# sensor-header.net
KiCad netlist of a schematic drawn in Altium Designer
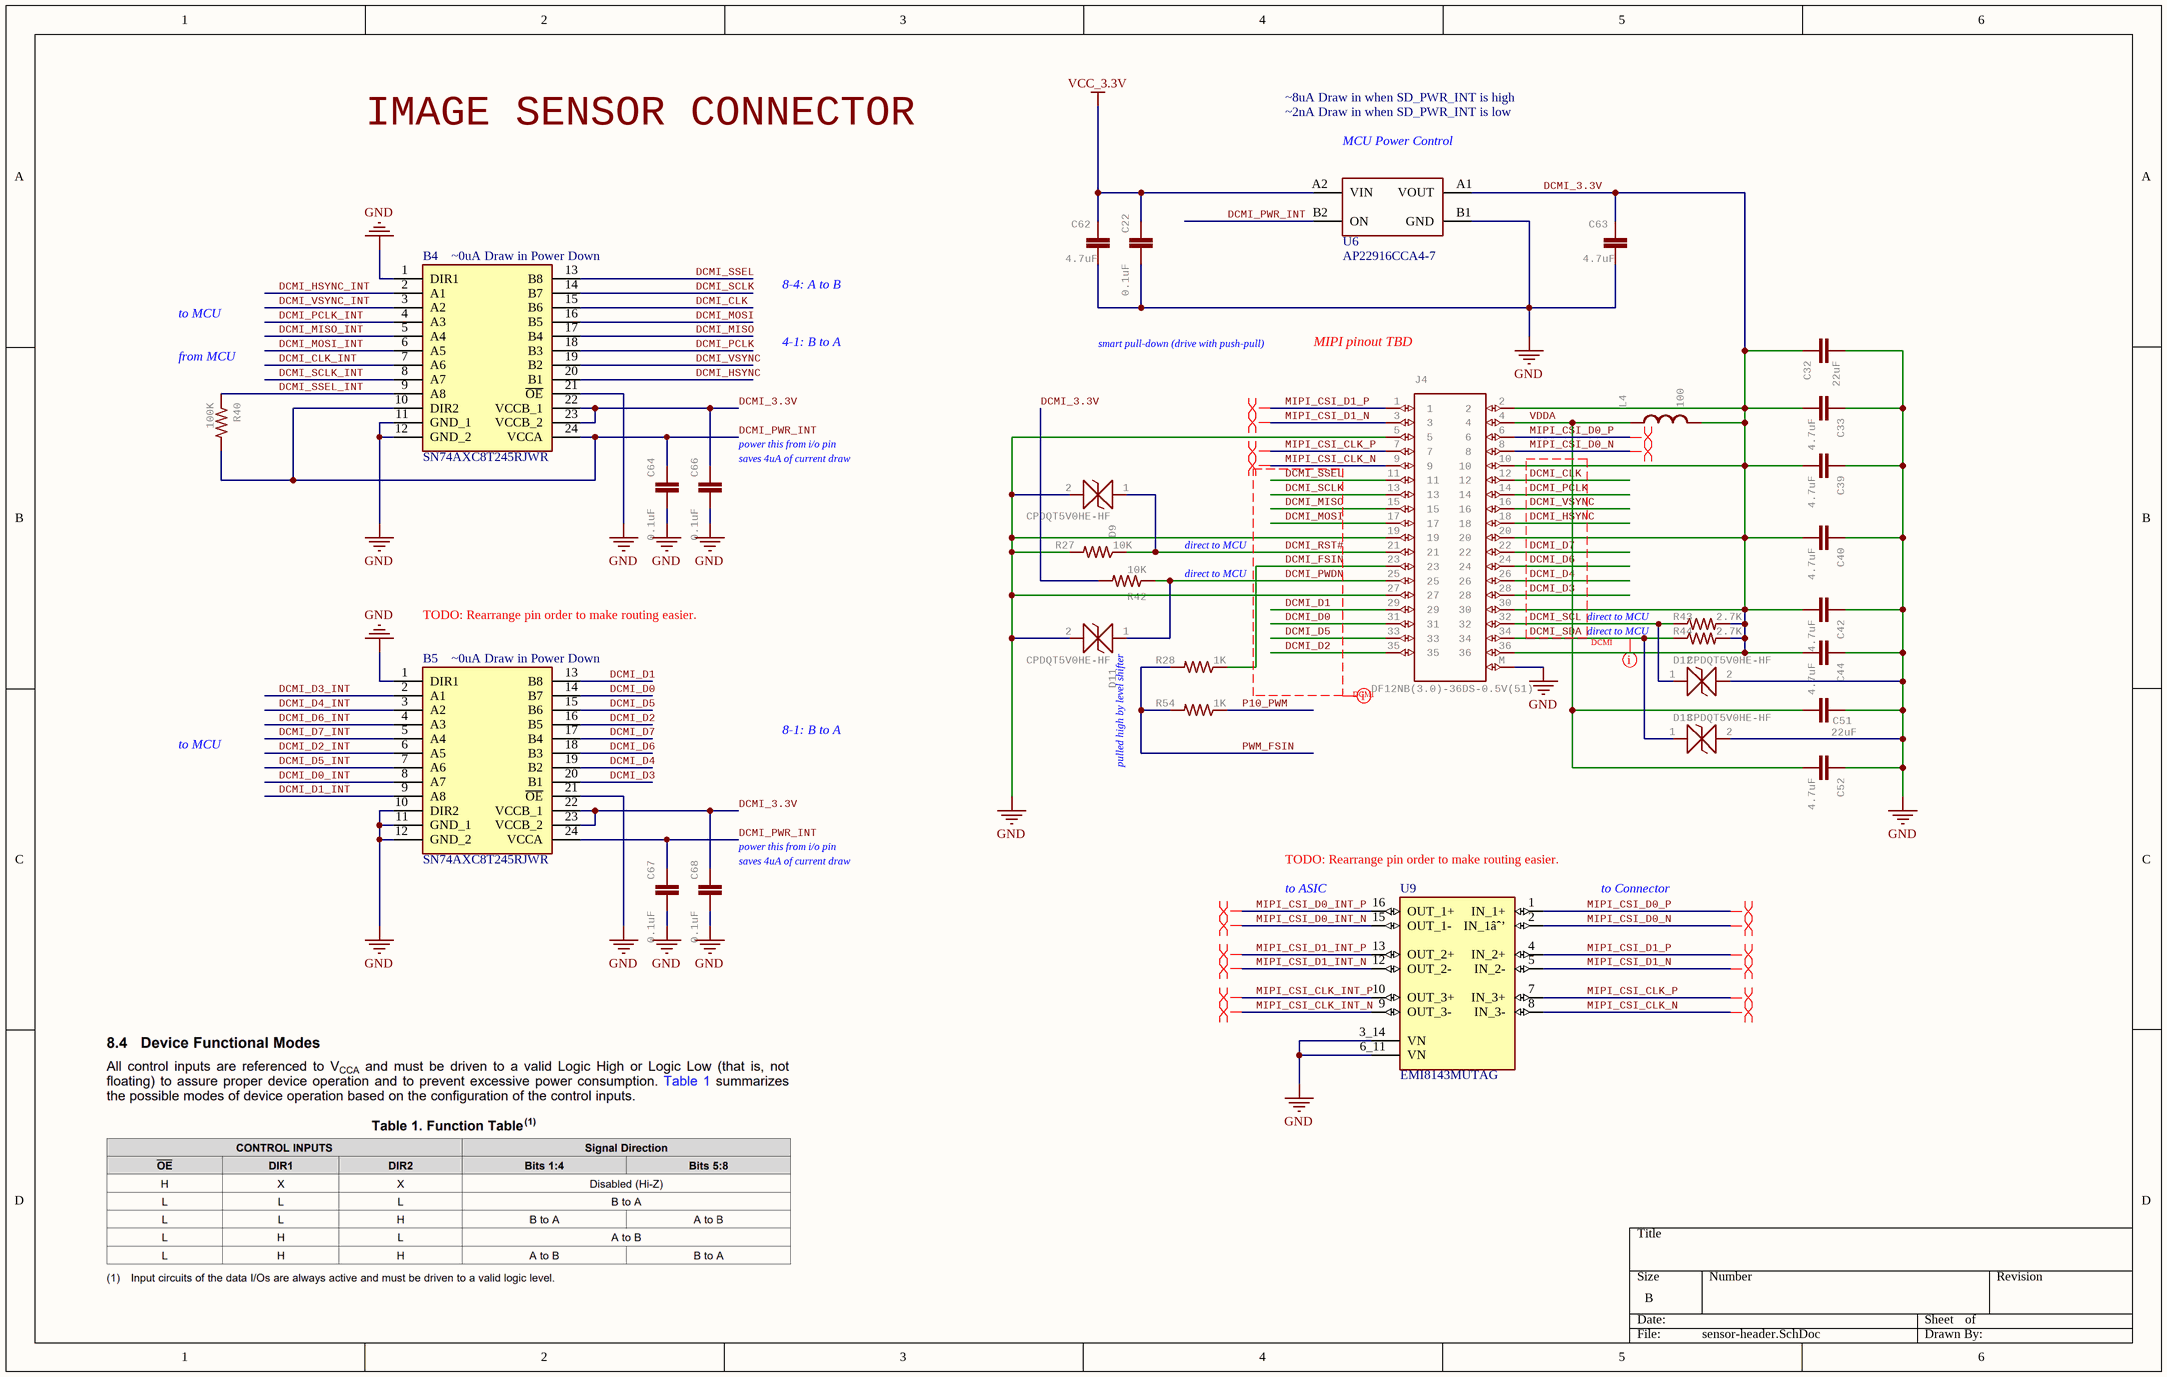
[diagram p0: sensor-header.SchDoc]

(export (version "E")
  (design (tool "Eeschema 10.0.6"))
  (components
    (comp (ref "B4")
      (value "SN74AXC8T245RJWR")
      (footprint "SN74AXC8T245RJWR")
      (description "8-Bit Dual-Supply Bus Transceiver")
      (fields (field (name "MOUSER PART NUMBER") "595-SN74AXC8T245RJWR"))
      (libsource (lib "openmv-ae3") (part "SN74AXC8T245RJWR"))
    )
    (comp (ref "B5")
      (value "SN74AXC8T245RJWR")
      (footprint "SN74AXC8T245RJWR")
      (description "8-Bit Dual-Supply Bus Transceiver")
      (fields (field (name "MOUSER PART NUMBER") "595-SN74AXC8T245RJWR"))
      (libsource (lib "openmv-ae3") (part "SN74AXC8T245RJWR"))
    )
    (comp (ref "C22")
      (value "0.1uF")
      (footprint "0402-CAP")
      (description "CAPACITOR, European symbol")
      (fields (field (name "MPN") "C0402C104Z4VAC"))
      (libsource (lib "openmv-ae3") (part "C-EUC0201"))
    )
    (comp (ref "C32")
      (value "22uF")
      (footprint "0805")
      (fields (field (name "MPN") "CL21A226MQQNNNE"))
      (libsource (lib "openmv-ae3") (part "22UF-0805-6.3V-20%"))
    )
    (comp (ref "C33")
      (value "4.7uF")
      (footprint "0402-CAP")
      (description "CapacitorStandard 0603 ceramic capacitor, and 0.1\" leaded capacitor.")
      (fields (field (name "MPN") "JMK105BBJ475MV-F") (field (name "LIBRARYNAME") "sfe"))
      (libsource (lib "openmv-ae3") (part "CAP0402-CAP"))
    )
    (comp (ref "C39")
      (value "4.7uF")
      (footprint "0402-CAP")
      (description "CapacitorStandard 0603 ceramic capacitor, and 0.1\" leaded capacitor.")
      (fields (field (name "MPN") "JMK105BBJ475MV-F") (field (name "LIBRARYNAME") "sfe"))
      (libsource (lib "openmv-ae3") (part "CAP0402-CAP"))
    )
    (comp (ref "C40")
      (value "4.7uF")
      (footprint "0402-CAP")
      (description "CapacitorStandard 0603 ceramic capacitor, and 0.1\" leaded capacitor.")
      (fields (field (name "MPN") "JMK105BBJ475MV-F") (field (name "LIBRARYNAME") "sfe"))
      (libsource (lib "openmv-ae3") (part "CAP0402-CAP"))
    )
    (comp (ref "C42")
      (value "4.7uF")
      (footprint "0402-CAP")
      (description "CapacitorStandard 0603 ceramic capacitor, and 0.1\" leaded capacitor.")
      (fields (field (name "MPN") "JMK105BBJ475MV-F") (field (name "LIBRARYNAME") "sfe"))
      (libsource (lib "openmv-ae3") (part "CAP0402-CAP"))
    )
    (comp (ref "C44")
      (value "4.7uF")
      (footprint "0402-CAP")
      (description "CapacitorStandard 0603 ceramic capacitor, and 0.1\" leaded capacitor.")
      (fields (field (name "MPN") "JMK105BBJ475MV-F") (field (name "LIBRARYNAME") "sfe"))
      (libsource (lib "openmv-ae3") (part "CAP0402-CAP"))
    )
    (comp (ref "C51")
      (value "22uF")
      (footprint "0805")
      (fields (field (name "MPN") "CL21A226MQQNNNE"))
      (libsource (lib "openmv-ae3") (part "22UF-0805-6.3V-20%"))
    )
    (comp (ref "C52")
      (value "4.7uF")
      (footprint "0402-CAP")
      (description "CapacitorStandard 0603 ceramic capacitor, and 0.1\" leaded capacitor.")
      (fields (field (name "MPN") "JMK105BBJ475MV-F") (field (name "LIBRARYNAME") "sfe"))
      (libsource (lib "openmv-ae3") (part "CAP0402-CAP"))
    )
    (comp (ref "C62")
      (value "4.7uF")
      (footprint "0402-CAP")
      (description "CapacitorStandard 0603 ceramic capacitor, and 0.1\" leaded capacitor.")
      (fields (field (name "MPN") "JMK105BBJ475MV-F") (field (name "LIBRARYNAME") "sfe"))
      (libsource (lib "") (part "CAP0402-CAP_1"))
    )
    (comp (ref "C63")
      (value "4.7uF")
      (footprint "0402-CAP")
      (description "CapacitorStandard 0603 ceramic capacitor, and 0.1\" leaded capacitor.")
      (fields (field (name "MPN") "JMK105BBJ475MV-F") (field (name "LIBRARYNAME") "sfe"))
      (libsource (lib "") (part "CAP0402-CAP_1"))
    )
    (comp (ref "C64")
      (value "0.1uF")
      (footprint "0402-CAP")
      (description "CAPACITOR, European symbol")
      (fields (field (name "MPN") "C0402C104Z4VAC"))
      (libsource (lib "openmv-ae3") (part "C-EUC0201"))
    )
    (comp (ref "C66")
      (value "0.1uF")
      (footprint "0402-CAP")
      (description "CAPACITOR, European symbol")
      (fields (field (name "MPN") "C0402C104Z4VAC"))
      (libsource (lib "openmv-ae3") (part "C-EUC0201"))
    )
    (comp (ref "C67")
      (value "0.1uF")
      (footprint "0402-CAP")
      (description "CAPACITOR, European symbol")
      (fields (field (name "MPN") "C0402C104Z4VAC"))
      (libsource (lib "openmv-ae3") (part "C-EUC0201"))
    )
    (comp (ref "C68")
      (value "0.1uF")
      (footprint "0402-CAP")
      (description "CAPACITOR, European symbol")
      (fields (field (name "MPN") "C0402C104Z4VAC"))
      (libsource (lib "openmv-ae3") (part "C-EUC0201"))
    )
    (comp (ref "D9")
      (value "CPDQT5V0HE-HF")
      (footprint "CPDQT5V0HEHF")
      (description "ESD Suppressors / TVS Diodes DIODE ESD 5VWM 65W 0402/SOD-923F   Source:  Datasheet")
      (fields (field (name "MOUSER_PART_NUMBER") "MOUSER_PART_NUMBER"))
      (libsource (lib "openmv-ae3") (part "CPDQT5V0HE-HF"))
    )
    (comp (ref "D11")
      (value "CPDQT5V0HE-HF")
      (footprint "CPDQT5V0HEHF")
      (description "ESD Suppressors / TVS Diodes DIODE ESD 5VWM 65W 0402/SOD-923F   Source:  Datasheet")
      (fields (field (name "MOUSER_PART_NUMBER") "MOUSER_PART_NUMBER"))
      (libsource (lib "openmv-ae3") (part "CPDQT5V0HE-HF"))
    )
    (comp (ref "D12")
      (value "CPDQT5V0HE-HF")
      (footprint "CPDQT5V0HEHF")
      (description "ESD Suppressors / TVS Diodes DIODE ESD 5VWM 65W 0402/SOD-923F   Source:  Datasheet")
      (fields (field (name "MOUSER_PART_NUMBER") "MOUSER_PART_NUMBER"))
      (libsource (lib "openmv-ae3") (part "CPDQT5V0HE-HF"))
    )
    (comp (ref "D13")
      (value "CPDQT5V0HE-HF")
      (footprint "CPDQT5V0HEHF")
      (description "ESD Suppressors / TVS Diodes DIODE ESD 5VWM 65W 0402/SOD-923F   Source:  Datasheet")
      (fields (field (name "MOUSER_PART_NUMBER") "MOUSER_PART_NUMBER"))
      (libsource (lib "openmv-ae3") (part "CPDQT5V0HE-HF"))
    )
    (comp (ref "J4")
      (value "DF12NB(3.0)-36DS-0.5V(51)")
      (footprint "DF12-36-DS")
      (description "Header")
      (libsource (lib "openmv-ae3") (part "DF12-36-DS"))
    )
    (comp (ref "L4")
      (value "100")
      (footprint "C0402")
      (fields (field (name "MPN") "MFBM1V1005-101-R") (field (name "LIBRARYNAME") "sfe"))
      (libsource (lib "openmv-ae3") (part "INDUCTOR0402"))
    )
    (comp (ref "R27")
      (value "10K")
      (footprint "R0201")
      (fields (field (name "LIBRARYNAME") "sfe"))
      (libsource (lib "openmv-ae3") (part "RESISTOR0402-RES"))
    )
    (comp (ref "R28")
      (value "1K")
      (footprint "R0201")
      (fields (field (name "LIBRARYNAME") "sfe"))
      (libsource (lib "openmv-ae3") (part "RESISTOR0402-RES"))
    )
    (comp (ref "R40")
      (value "100K")
      (footprint "R0201")
      (fields (field (name "LIBRARYNAME") "sfe"))
      (libsource (lib "openmv-ae3") (part "RESISTOR0402-RES"))
    )
    (comp (ref "R42")
      (value "10K")
      (footprint "R0201")
      (fields (field (name "LIBRARYNAME") "sfe"))
      (libsource (lib "openmv-ae3") (part "RESISTOR0402-RES"))
    )
    (comp (ref "R43")
      (value "2.7K")
      (footprint "R0201")
      (fields (field (name "LIBRARYNAME") "sfe"))
      (libsource (lib "openmv-ae3") (part "RESISTOR0402-RES"))
    )
    (comp (ref "R44")
      (value "2.7K")
      (footprint "R0201")
      (fields (field (name "LIBRARYNAME") "sfe"))
      (libsource (lib "openmv-ae3") (part "RESISTOR0402-RES"))
    )
    (comp (ref "R54")
      (value "1K")
      (footprint "R0201")
      (fields (field (name "LIBRARYNAME") "sfe"))
      (libsource (lib "openmv-ae3") (part "RESISTOR0402-RES"))
    )
    (comp (ref "U6")
      (value "PMOS Load Switch")
      (footprint "AP22916CCA4-7")
      (fields (field (name "MPN") "AP22916CCA4-7") (field (name "MF") "Diodes Inc"))
      (libsource (lib "openmv-ae3") (part "AP22916CCA4-7"))
    )
    (comp (ref "U9")
      (value "EMI8143MUTAG")
      (footprint "IC_EMI8143MUTAG")
      (description "6 Line Common Mode Choke Surface Mount 100mA DCR 6Ohm (Typ)")
      (fields
        (field (name "MF") "ON Semiconductor")
        (field (name "DIGI-KEY_PART_NUMBER") "EMI8143MUTAGOSCT-ND")
      )
      (libsource (lib "openmv-ae3") (part "CMP-008-000000-1"))
    )
  )
  (nets
    (net (code "1") (name "/DCMI_3.3V") (class "Default")
      (node (ref "B4") (pin "22") (pinfunction "VCCB_1_22") (pintype "passive"))
      (node (ref "B4") (pin "23") (pinfunction "VCCB_2_23") (pintype "passive"))
      (node (ref "B5") (pin "22") (pinfunction "VCCB_1_22") (pintype "passive"))
      (node (ref "B5") (pin "23") (pinfunction "VCCB_2_23") (pintype "passive"))
      (node (ref "C32") (pin "1") (pinfunction "1_1") (pintype "passive"))
      (node (ref "C33") (pin "2") (pinfunction "2_2") (pintype "passive"))
      (node (ref "C39") (pin "2") (pinfunction "2_2") (pintype "passive"))
      (node (ref "C40") (pin "2") (pinfunction "2_2") (pintype "passive"))
      (node (ref "C42") (pin "2") (pinfunction "2_2") (pintype "passive"))
      (node (ref "C44") (pin "2") (pinfunction "2_2") (pintype "passive"))
      (node (ref "C63") (pin "1") (pinfunction "1_1") (pintype "passive"))
      (node (ref "C66") (pin "1") (pinfunction "1_1") (pintype "passive"))
      (node (ref "C68") (pin "1") (pinfunction "1_1") (pintype "passive"))
      (node (ref "J4") (pin "10") (pinfunction "10_10") (pintype "bidirectional"))
      (node (ref "J4") (pin "2") (pinfunction "2_2") (pintype "bidirectional"))
      (node (ref "J4") (pin "20") (pinfunction "20_20") (pintype "bidirectional"))
      (node (ref "J4") (pin "30") (pinfunction "30_30") (pintype "bidirectional"))
      (node (ref "J4") (pin "36") (pinfunction "36_36") (pintype "bidirectional"))
      (node (ref "L4") (pin "2") (pinfunction "2_2") (pintype "passive"))
      (node (ref "R42") (pin "2") (pinfunction "2_2") (pintype "passive"))
      (node (ref "R43") (pin "2") (pinfunction "2_2") (pintype "passive"))
      (node (ref "R44") (pin "2") (pinfunction "2_2") (pintype "passive"))
      (node (ref "U6") (pin "A1") (pinfunction "VOUT_A1") (pintype "passive"))
    )
    (net (code "2") (name "/DCMI_CLK") (class "Default")
      (node (ref "B4") (pin "15") (pinfunction "B6_15") (pintype "passive"))
      (node (ref "J4") (pin "12") (pinfunction "12_12") (pintype "bidirectional"))
    )
    (net (code "3") (name "/DCMI_CLK_INT") (class "Default")
      (node (ref "B4") (pin "7") (pinfunction "A6_7") (pintype "passive"))
    )
    (net (code "4") (name "/DCMI_D0") (class "Default")
      (node (ref "B5") (pin "14") (pinfunction "B7_14") (pintype "passive"))
      (node (ref "J4") (pin "31") (pinfunction "31_31") (pintype "bidirectional"))
    )
    (net (code "5") (name "/DCMI_D0_INT") (class "Default")
      (node (ref "B5") (pin "8") (pinfunction "A7_8") (pintype "passive"))
    )
    (net (code "6") (name "/DCMI_D1") (class "Default")
      (node (ref "B5") (pin "13") (pinfunction "B8_13") (pintype "passive"))
      (node (ref "J4") (pin "29") (pinfunction "29_29") (pintype "bidirectional"))
    )
    (net (code "7") (name "/DCMI_D1_INT") (class "Default")
      (node (ref "B5") (pin "9") (pinfunction "A8_9") (pintype "passive"))
    )
    (net (code "8") (name "/DCMI_D2") (class "Default")
      (node (ref "B5") (pin "16") (pinfunction "B5_16") (pintype "passive"))
      (node (ref "J4") (pin "35") (pinfunction "35_35") (pintype "bidirectional"))
    )
    (net (code "9") (name "/DCMI_D2_INT") (class "Default")
      (node (ref "B5") (pin "6") (pinfunction "A5_6") (pintype "passive"))
    )
    (net (code "10") (name "/DCMI_D3") (class "Default")
      (node (ref "B5") (pin "20") (pinfunction "B1_20") (pintype "passive"))
      (node (ref "J4") (pin "28") (pinfunction "28_28") (pintype "bidirectional"))
    )
    (net (code "11") (name "/DCMI_D3_INT") (class "Default")
      (node (ref "B5") (pin "2") (pinfunction "A1_2") (pintype "passive"))
    )
    (net (code "12") (name "/DCMI_D4") (class "Default")
      (node (ref "B5") (pin "19") (pinfunction "B2_19") (pintype "passive"))
      (node (ref "J4") (pin "26") (pinfunction "26_26") (pintype "bidirectional"))
    )
    (net (code "13") (name "/DCMI_D4_INT") (class "Default")
      (node (ref "B5") (pin "3") (pinfunction "A2_3") (pintype "passive"))
    )
    (net (code "14") (name "/DCMI_D5") (class "Default")
      (node (ref "B5") (pin "15") (pinfunction "B6_15") (pintype "passive"))
      (node (ref "J4") (pin "33") (pinfunction "33_33") (pintype "bidirectional"))
    )
    (net (code "15") (name "/DCMI_D5_INT") (class "Default")
      (node (ref "B5") (pin "7") (pinfunction "A6_7") (pintype "passive"))
    )
    (net (code "16") (name "/DCMI_D6") (class "Default")
      (node (ref "B5") (pin "18") (pinfunction "B3_18") (pintype "passive"))
      (node (ref "J4") (pin "24") (pinfunction "24_24") (pintype "bidirectional"))
    )
    (net (code "17") (name "/DCMI_D6_INT") (class "Default")
      (node (ref "B5") (pin "4") (pinfunction "A3_4") (pintype "passive"))
    )
    (net (code "18") (name "/DCMI_D7") (class "Default")
      (node (ref "B5") (pin "17") (pinfunction "B4_17") (pintype "passive"))
      (node (ref "J4") (pin "22") (pinfunction "22_22") (pintype "bidirectional"))
    )
    (net (code "19") (name "/DCMI_D7_INT") (class "Default")
      (node (ref "B5") (pin "5") (pinfunction "A4_5") (pintype "passive"))
    )
    (net (code "20") (name "/DCMI_FSIN") (class "Default")
      (node (ref "J4") (pin "23") (pinfunction "23_23") (pintype "bidirectional"))
      (node (ref "R28") (pin "1") (pinfunction "1_1") (pintype "passive"))
    )
    (net (code "21") (name "/DCMI_HSYNC") (class "Default")
      (node (ref "B4") (pin "20") (pinfunction "B1_20") (pintype "passive"))
      (node (ref "J4") (pin "18") (pinfunction "18_18") (pintype "bidirectional"))
    )
    (net (code "22") (name "/DCMI_HSYNC_INT") (class "Default")
      (node (ref "B4") (pin "2") (pinfunction "A1_2") (pintype "passive"))
    )
    (net (code "23") (name "/DCMI_MISO") (class "Default")
      (node (ref "B4") (pin "17") (pinfunction "B4_17") (pintype "passive"))
      (node (ref "J4") (pin "15") (pinfunction "15_15") (pintype "bidirectional"))
    )
    (net (code "24") (name "/DCMI_MISO_INT") (class "Default")
      (node (ref "B4") (pin "5") (pinfunction "A4_5") (pintype "passive"))
    )
    (net (code "25") (name "/DCMI_MOSI") (class "Default")
      (node (ref "B4") (pin "16") (pinfunction "B5_16") (pintype "passive"))
      (node (ref "J4") (pin "17") (pinfunction "17_17") (pintype "bidirectional"))
    )
    (net (code "26") (name "/DCMI_MOSI_INT") (class "Default")
      (node (ref "B4") (pin "6") (pinfunction "A5_6") (pintype "passive"))
    )
    (net (code "27") (name "/DCMI_PCLK") (class "Default")
      (node (ref "B4") (pin "18") (pinfunction "B3_18") (pintype "passive"))
      (node (ref "J4") (pin "14") (pinfunction "14_14") (pintype "bidirectional"))
    )
    (net (code "28") (name "/DCMI_PCLK_INT") (class "Default")
      (node (ref "B4") (pin "4") (pinfunction "A3_4") (pintype "passive"))
    )
    (net (code "29") (name "/DCMI_PWDN") (class "Default")
      (node (ref "D11") (pin "1") (pinfunction "1_1") (pintype "bidirectional"))
      (node (ref "J4") (pin "25") (pinfunction "25_25") (pintype "bidirectional"))
      (node (ref "R42") (pin "1") (pinfunction "1_1") (pintype "passive"))
    )
    (net (code "30") (name "/DCMI_PWR_INT") (class "Default")
      (node (ref "B4") (pin "10") (pinfunction "DIR2_10") (pintype "passive"))
      (node (ref "B4") (pin "24") (pinfunction "VCCA_24") (pintype "passive"))
      (node (ref "B5") (pin "24") (pinfunction "VCCA_24") (pintype "passive"))
      (node (ref "C64") (pin "1") (pinfunction "1_1") (pintype "passive"))
      (node (ref "C67") (pin "1") (pinfunction "1_1") (pintype "passive"))
      (node (ref "R40") (pin "2") (pinfunction "2_2") (pintype "passive"))
      (node (ref "U6") (pin "B2") (pinfunction "ON_B2") (pintype "passive"))
    )
    (net (code "31") (name "/DCMI_RST#") (class "Default")
      (node (ref "D9") (pin "1") (pinfunction "1_1") (pintype "bidirectional"))
      (node (ref "J4") (pin "21") (pinfunction "21_21") (pintype "bidirectional"))
      (node (ref "R27") (pin "1") (pinfunction "1_1") (pintype "passive"))
    )
    (net (code "32") (name "/DCMI_SCL") (class "Default")
      (node (ref "D12") (pin "1") (pinfunction "1_1") (pintype "bidirectional"))
      (node (ref "J4") (pin "32") (pinfunction "32_32") (pintype "bidirectional"))
      (node (ref "R43") (pin "1") (pinfunction "1_1") (pintype "passive"))
    )
    (net (code "33") (name "/DCMI_SCLK") (class "Default")
      (node (ref "B4") (pin "14") (pinfunction "B7_14") (pintype "passive"))
      (node (ref "J4") (pin "13") (pinfunction "13_13") (pintype "bidirectional"))
    )
    (net (code "34") (name "/DCMI_SCLK_INT") (class "Default")
      (node (ref "B4") (pin "8") (pinfunction "A7_8") (pintype "passive"))
    )
    (net (code "35") (name "/DCMI_SDA") (class "Default")
      (node (ref "D13") (pin "1") (pinfunction "1_1") (pintype "bidirectional"))
      (node (ref "J4") (pin "34") (pinfunction "34_34") (pintype "bidirectional"))
      (node (ref "R44") (pin "1") (pinfunction "1_1") (pintype "passive"))
    )
    (net (code "36") (name "/DCMI_SSEL") (class "Default")
      (node (ref "B4") (pin "13") (pinfunction "B8_13") (pintype "passive"))
      (node (ref "J4") (pin "11") (pinfunction "11_11") (pintype "bidirectional"))
    )
    (net (code "37") (name "/DCMI_SSEL_INT") (class "Default")
      (node (ref "B4") (pin "9") (pinfunction "A8_9") (pintype "passive"))
      (node (ref "R40") (pin "1") (pinfunction "1_1") (pintype "passive"))
    )
    (net (code "38") (name "/DCMI_VSYNC") (class "Default")
      (node (ref "B4") (pin "19") (pinfunction "B2_19") (pintype "passive"))
      (node (ref "J4") (pin "16") (pinfunction "16_16") (pintype "bidirectional"))
    )
    (net (code "39") (name "/DCMI_VSYNC_INT") (class "Default")
      (node (ref "B4") (pin "3") (pinfunction "A2_3") (pintype "passive"))
    )
    (net (code "40") (name "/MIPI_CSI_CLK_INT_N") (class "Default")
      (node (ref "U9") (pin "9") (pinfunction "OUT_3-_9") (pintype "bidirectional"))
    )
    (net (code "41") (name "/MIPI_CSI_CLK_INT_P") (class "Default")
      (node (ref "U9") (pin "10") (pinfunction "OUT_3+_10") (pintype "bidirectional"))
    )
    (net (code "42") (name "/MIPI_CSI_CLK_N") (class "Default")
      (node (ref "J4") (pin "9") (pinfunction "9_9") (pintype "bidirectional"))
      (node (ref "U9") (pin "8") (pinfunction "IN_3-_8") (pintype "bidirectional"))
    )
    (net (code "43") (name "/MIPI_CSI_CLK_P") (class "Default")
      (node (ref "J4") (pin "7") (pinfunction "7_7") (pintype "bidirectional"))
      (node (ref "U9") (pin "7") (pinfunction "IN_3+_7") (pintype "bidirectional"))
    )
    (net (code "44") (name "/MIPI_CSI_D0_INT_N") (class "Default")
      (node (ref "U9") (pin "15") (pinfunction "OUT_1-_15") (pintype "bidirectional"))
    )
    (net (code "45") (name "/MIPI_CSI_D0_INT_P") (class "Default")
      (node (ref "U9") (pin "16") (pinfunction "OUT_1+_16") (pintype "bidirectional"))
    )
    (net (code "46") (name "/MIPI_CSI_D0_N") (class "Default")
      (node (ref "J4") (pin "8") (pinfunction "8_8") (pintype "bidirectional"))
      (node (ref "U9") (pin "2") (pinfunction "IN_1âˆ’_2") (pintype "bidirectional"))
    )
    (net (code "47") (name "/MIPI_CSI_D0_P") (class "Default")
      (node (ref "J4") (pin "6") (pinfunction "6_6") (pintype "bidirectional"))
      (node (ref "U9") (pin "1") (pinfunction "IN_1+_1") (pintype "bidirectional"))
    )
    (net (code "48") (name "/MIPI_CSI_D1_INT_N") (class "Default")
      (node (ref "U9") (pin "12") (pinfunction "OUT_2-_12") (pintype "bidirectional"))
    )
    (net (code "49") (name "/MIPI_CSI_D1_INT_P") (class "Default")
      (node (ref "U9") (pin "13") (pinfunction "OUT_2+_13") (pintype "bidirectional"))
    )
    (net (code "50") (name "/MIPI_CSI_D1_N") (class "Default")
      (node (ref "J4") (pin "3") (pinfunction "3_3") (pintype "bidirectional"))
      (node (ref "U9") (pin "5") (pinfunction "IN_2-_5") (pintype "bidirectional"))
    )
    (net (code "51") (name "/MIPI_CSI_D1_P") (class "Default")
      (node (ref "J4") (pin "1") (pinfunction "1_1") (pintype "bidirectional"))
      (node (ref "U9") (pin "4") (pinfunction "IN_2+_4") (pintype "bidirectional"))
    )
    (net (code "52") (name "/P10_PWM") (class "Default")
      (node (ref "R54") (pin "1") (pinfunction "1_1") (pintype "passive"))
    )
    (net (code "53") (name "/PWM_FSIN") (class "Default")
      (node (ref "R28") (pin "2") (pinfunction "2_2") (pintype "passive"))
      (node (ref "R54") (pin "2") (pinfunction "2_2") (pintype "passive"))
    )
    (net (code "54") (name "/VDDA") (class "Default")
      (node (ref "C51") (pin "1") (pinfunction "1_1") (pintype "passive"))
      (node (ref "C52") (pin "2") (pinfunction "2_2") (pintype "passive"))
      (node (ref "J4") (pin "4") (pinfunction "4_4") (pintype "bidirectional"))
      (node (ref "L4") (pin "1") (pinfunction "1_1") (pintype "passive"))
    )
    (net (code "55") (name "GND") (class "Default")
      (node (ref "B4") (pin "1") (pinfunction "DIR1_1") (pintype "passive"))
      (node (ref "B4") (pin "11") (pinfunction "GND_1_11") (pintype "passive"))
      (node (ref "B4") (pin "12") (pinfunction "GND_2_12") (pintype "passive"))
      (node (ref "B4") (pin "21") (pinfunction "~{OE}_21") (pintype "passive"))
      (node (ref "B5") (pin "1") (pinfunction "DIR1_1") (pintype "passive"))
      (node (ref "B5") (pin "10") (pinfunction "DIR2_10") (pintype "passive"))
      (node (ref "B5") (pin "11") (pinfunction "GND_1_11") (pintype "passive"))
      (node (ref "B5") (pin "12") (pinfunction "GND_2_12") (pintype "passive"))
      (node (ref "B5") (pin "21") (pinfunction "~{OE}_21") (pintype "passive"))
      (node (ref "C22") (pin "2") (pinfunction "2_2") (pintype "passive"))
      (node (ref "C32") (pin "2") (pinfunction "2_2") (pintype "passive"))
      (node (ref "C33") (pin "1") (pinfunction "1_1") (pintype "passive"))
      (node (ref "C39") (pin "1") (pinfunction "1_1") (pintype "passive"))
      (node (ref "C40") (pin "1") (pinfunction "1_1") (pintype "passive"))
      (node (ref "C42") (pin "1") (pinfunction "1_1") (pintype "passive"))
      (node (ref "C44") (pin "1") (pinfunction "1_1") (pintype "passive"))
      (node (ref "C51") (pin "2") (pinfunction "2_2") (pintype "passive"))
      (node (ref "C52") (pin "1") (pinfunction "1_1") (pintype "passive"))
      (node (ref "C62") (pin "2") (pinfunction "2_2") (pintype "passive"))
      (node (ref "C63") (pin "2") (pinfunction "2_2") (pintype "passive"))
      (node (ref "C64") (pin "2") (pinfunction "2_2") (pintype "passive"))
      (node (ref "C66") (pin "2") (pinfunction "2_2") (pintype "passive"))
      (node (ref "C67") (pin "2") (pinfunction "2_2") (pintype "passive"))
      (node (ref "C68") (pin "2") (pinfunction "2_2") (pintype "passive"))
      (node (ref "D11") (pin "2") (pinfunction "2_2") (pintype "bidirectional"))
      (node (ref "D12") (pin "2") (pinfunction "2_2") (pintype "bidirectional"))
      (node (ref "D13") (pin "2") (pinfunction "2_2") (pintype "bidirectional"))
      (node (ref "D9") (pin "2") (pinfunction "2_2") (pintype "bidirectional"))
      (node (ref "J4") (pin "19") (pinfunction "19_19") (pintype "bidirectional"))
      (node (ref "J4") (pin "27") (pinfunction "27_27") (pintype "bidirectional"))
      (node (ref "J4") (pin "5") (pinfunction "5_5") (pintype "bidirectional"))
      (node (ref "J4") (pin "M") (pinfunction "M_M") (pintype "bidirectional"))
      (node (ref "R27") (pin "2") (pinfunction "2_2") (pintype "passive"))
      (node (ref "U6") (pin "B1") (pinfunction "GND_B1") (pintype "passive"))
      (node (ref "U9") (pin "3_14") (pinfunction "VN_3_14") (pintype "power_in"))
      (node (ref "U9") (pin "6_11") (pinfunction "VN_6_11") (pintype "power_in"))
    )
    (net (code "56") (name "VCC_3.3V") (class "Default")
      (node (ref "C22") (pin "1") (pinfunction "1_1") (pintype "passive"))
      (node (ref "C62") (pin "1") (pinfunction "1_1") (pintype "passive"))
      (node (ref "U6") (pin "A2") (pinfunction "VIN_A2") (pintype "passive"))
    )
  )
)
